# mini-MIDI-hub.net
KiCad netlist of a schematic drawn in EAGLE
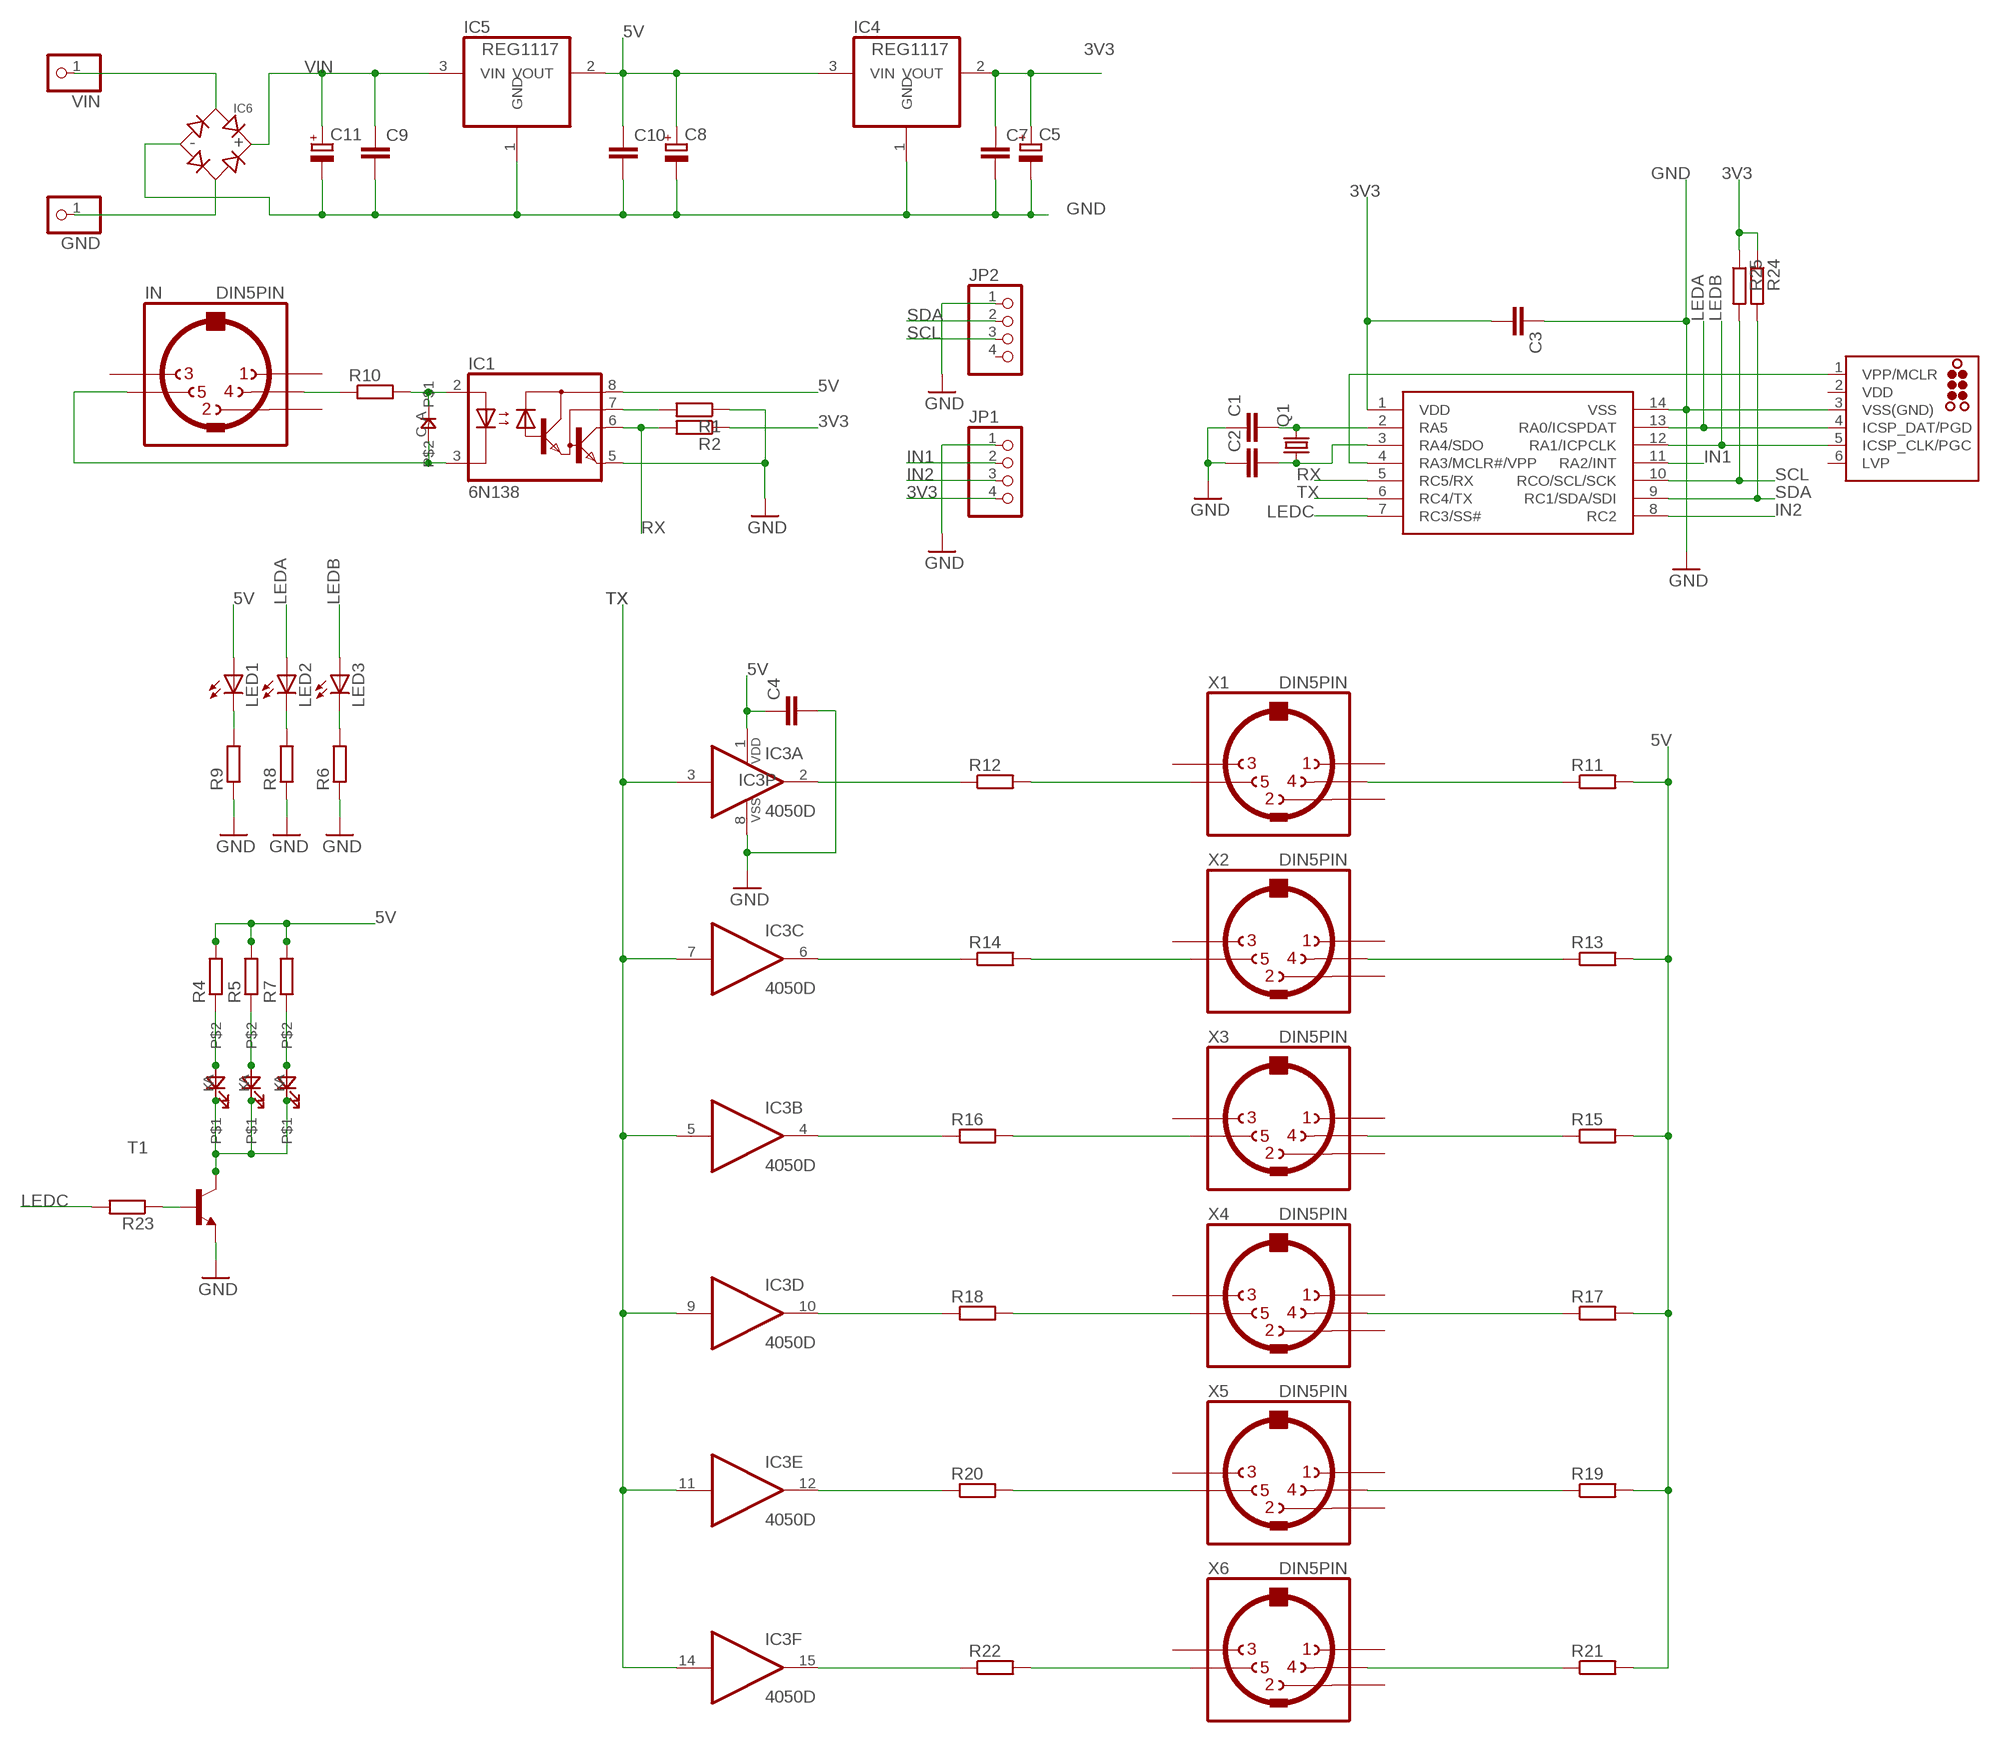
[diagram p0: schematic, sheet 1]

(export (version "E")
  (design (tool "Eeschema 10.0.6"))
  (components
    (comp (ref "C1")
      (value "C-EUC0805")
      (footprint "eagle-import:C0805")
      (libsource (lib "eagle-import") (part "C-EUC0805"))
    )
    (comp (ref "C2")
      (value "C-EUC0805")
      (footprint "eagle-import:C0805")
      (libsource (lib "eagle-import") (part "C-EUC0805"))
    )
    (comp (ref "C3")
      (value "C-EUC0805")
      (footprint "eagle-import:C0805")
      (libsource (lib "eagle-import") (part "C-EUC0805"))
    )
    (comp (ref "C4")
      (value "C-EUC0805")
      (footprint "eagle-import:C0805")
      (libsource (lib "eagle-import") (part "C-EUC0805"))
    )
    (comp (ref "C5")
      (value "CPOL-EUE2-4")
      (footprint "eagle-import:E2-4")
      (libsource (lib "eagle-import") (part "CPOL-EUE2-4"))
    )
    (comp (ref "C7")
      (value "C-EUC0805")
      (footprint "eagle-import:C0805")
      (libsource (lib "eagle-import") (part "C-EUC0805"))
    )
    (comp (ref "C8")
      (value "CPOL-EUE2-4")
      (footprint "eagle-import:E2-4")
      (libsource (lib "eagle-import") (part "CPOL-EUE2-4"))
    )
    (comp (ref "C9")
      (value "C-EUC0805")
      (footprint "eagle-import:C0805")
      (libsource (lib "eagle-import") (part "C-EUC0805"))
    )
    (comp (ref "C10")
      (value "C-EUC0805")
      (footprint "eagle-import:C0805")
      (libsource (lib "eagle-import") (part "C-EUC0805"))
    )
    (comp (ref "C11")
      (value "CPOL-EUE2-4")
      (footprint "eagle-import:E2-4")
      (libsource (lib "eagle-import") (part "CPOL-EUE2-4"))
    )
    (comp (ref "D1")
      (value "0805DIODE")
      (footprint "eagle-import:0805DIODE")
      (libsource (lib "eagle-import") (part "0805DIODE"))
    )
    (comp (ref "GND")
      (value "PINHD-1X1")
      (footprint "eagle-import:1X01")
      (libsource (lib "eagle-import") (part "PINHD-1X1"))
    )
    (comp (ref "IC1")
      (value "6N138")
      (footprint "eagle-import:DIL08")
      (fields (field (name "MF") "VISHAY/TELEFUNKEN"))
      (libsource (lib "eagle-import") (part "6N138"))
    )
    (comp (ref "IC2")
      (value "PIC16F1825SO14")
      (footprint "eagle-import:SO14")
      (libsource (lib "eagle-import") (part "PIC16F1825SO14"))
    )
    (comp (ref "IC3")
      (value "4050D")
      (footprint "eagle-import:SO16")
      (libsource (lib "eagle-import") (part "4050D"))
    )
    (comp (ref "IC4")
      (value "REG1117")
      (footprint "eagle-import:SOT223")
      (libsource (lib "eagle-import") (part "REG1117"))
    )
    (comp (ref "IC5")
      (value "REG1117")
      (footprint "eagle-import:SOT223")
      (libsource (lib "eagle-import") (part "REG1117"))
    )
    (comp (ref "IC6")
      (value "BRIDGERECTIFIER")
      (footprint "eagle-import:SOIC-4")
      (libsource (lib "eagle-import") (part "BRIDGERECTIFIER"))
    )
    (comp (ref "ICSP")
      (value "TC2030-MCP-NL")
      (footprint "eagle-import:TC2030-MCP-NL")
      (libsource (lib "eagle-import") (part "TC2030-MCP-NL"))
    )
    (comp (ref "IN")
      (value "DIN5PIN")
      (footprint "eagle-import:EDGEDIN")
      (libsource (lib "eagle-import") (part "DIN5PIN"))
    )
    (comp (ref "JP1")
      (value "PINHD-1X4")
      (footprint "eagle-import:1X04")
      (libsource (lib "eagle-import") (part "PINHD-1X4"))
    )
    (comp (ref "JP2")
      (value "PINHD-1X4")
      (footprint "eagle-import:1X04")
      (libsource (lib "eagle-import") (part "PINHD-1X4"))
    )
    (comp (ref "LED1")
      (value "LED3MM")
      (footprint "eagle-import:LED3MM")
      (libsource (lib "eagle-import") (part "LED3MM"))
    )
    (comp (ref "LED2")
      (value "LED3MM")
      (footprint "eagle-import:LED3MM")
      (libsource (lib "eagle-import") (part "LED3MM"))
    )
    (comp (ref "LED3")
      (value "LED3MM")
      (footprint "eagle-import:LED3MM")
      (libsource (lib "eagle-import") (part "LED3MM"))
    )
    (comp (ref "Q1")
      (value "CRYSTALHC49S")
      (footprint "eagle-import:HC49_S")
      (libsource (lib "eagle-import") (part "CRYSTALHC49S"))
    )
    (comp (ref "R1")
      (value "R-EU_R0805")
      (footprint "eagle-import:R0805")
      (libsource (lib "eagle-import") (part "R-EU_R0805"))
    )
    (comp (ref "R2")
      (value "R-EU_R0805")
      (footprint "eagle-import:R0805")
      (libsource (lib "eagle-import") (part "R-EU_R0805"))
    )
    (comp (ref "R4")
      (value "R-EU_R0805")
      (footprint "eagle-import:R0805")
      (libsource (lib "eagle-import") (part "R-EU_R0805"))
    )
    (comp (ref "R5")
      (value "R-EU_R0805")
      (footprint "eagle-import:R0805")
      (libsource (lib "eagle-import") (part "R-EU_R0805"))
    )
    (comp (ref "R6")
      (value "R-EU_R0805")
      (footprint "eagle-import:R0805")
      (libsource (lib "eagle-import") (part "R-EU_R0805"))
    )
    (comp (ref "R7")
      (value "R-EU_R0805")
      (footprint "eagle-import:R0805")
      (libsource (lib "eagle-import") (part "R-EU_R0805"))
    )
    (comp (ref "R8")
      (value "R-EU_R0805")
      (footprint "eagle-import:R0805")
      (libsource (lib "eagle-import") (part "R-EU_R0805"))
    )
    (comp (ref "R9")
      (value "R-EU_R0805")
      (footprint "eagle-import:R0805")
      (libsource (lib "eagle-import") (part "R-EU_R0805"))
    )
    (comp (ref "R10")
      (value "R-EU_R0805")
      (footprint "eagle-import:R0805")
      (libsource (lib "eagle-import") (part "R-EU_R0805"))
    )
    (comp (ref "R11")
      (value "R-EU_R0805")
      (footprint "eagle-import:R0805")
      (libsource (lib "eagle-import") (part "R-EU_R0805"))
    )
    (comp (ref "R12")
      (value "R-EU_R0805")
      (footprint "eagle-import:R0805")
      (libsource (lib "eagle-import") (part "R-EU_R0805"))
    )
    (comp (ref "R13")
      (value "R-EU_R0805")
      (footprint "eagle-import:R0805")
      (libsource (lib "eagle-import") (part "R-EU_R0805"))
    )
    (comp (ref "R14")
      (value "R-EU_R0805")
      (footprint "eagle-import:R0805")
      (libsource (lib "eagle-import") (part "R-EU_R0805"))
    )
    (comp (ref "R15")
      (value "R-EU_R0805")
      (footprint "eagle-import:R0805")
      (libsource (lib "eagle-import") (part "R-EU_R0805"))
    )
    (comp (ref "R16")
      (value "R-EU_R0805")
      (footprint "eagle-import:R0805")
      (libsource (lib "eagle-import") (part "R-EU_R0805"))
    )
    (comp (ref "R17")
      (value "R-EU_R0805")
      (footprint "eagle-import:R0805")
      (libsource (lib "eagle-import") (part "R-EU_R0805"))
    )
    (comp (ref "R18")
      (value "R-EU_R0805")
      (footprint "eagle-import:R0805")
      (libsource (lib "eagle-import") (part "R-EU_R0805"))
    )
    (comp (ref "R19")
      (value "R-EU_R0805")
      (footprint "eagle-import:R0805")
      (libsource (lib "eagle-import") (part "R-EU_R0805"))
    )
    (comp (ref "R20")
      (value "R-EU_R0805")
      (footprint "eagle-import:R0805")
      (libsource (lib "eagle-import") (part "R-EU_R0805"))
    )
    (comp (ref "R21")
      (value "R-EU_R0805")
      (footprint "eagle-import:R0805")
      (libsource (lib "eagle-import") (part "R-EU_R0805"))
    )
    (comp (ref "R22")
      (value "R-EU_R0805")
      (footprint "eagle-import:R0805")
      (libsource (lib "eagle-import") (part "R-EU_R0805"))
    )
    (comp (ref "R23")
      (value "R-EU_R0805")
      (footprint "eagle-import:R0805")
      (libsource (lib "eagle-import") (part "R-EU_R0805"))
    )
    (comp (ref "R24")
      (value "R-EU_R0805")
      (footprint "eagle-import:R0805")
      (libsource (lib "eagle-import") (part "R-EU_R0805"))
    )
    (comp (ref "R25")
      (value "R-EU_R0805")
      (footprint "eagle-import:R0805")
      (libsource (lib "eagle-import") (part "R-EU_R0805"))
    )
    (comp (ref "T1")
      (value "MMBT3904LT1-NPN-SOT23-BEC")
      (footprint "eagle-import:SOT23-BEC")
      (libsource (lib "eagle-import") (part "-NPN-SOT23-BECMMBT3904LT1"))
    )
    (comp (ref "U$2")
      (value "LED5MM_EDGE")
      (footprint "eagle-import:LED5MM_EDGE")
      (libsource (lib "eagle-import") (part "LED5MM_EDGE"))
    )
    (comp (ref "U$3")
      (value "LED5MM_EDGE")
      (footprint "eagle-import:LED5MM_EDGE")
      (libsource (lib "eagle-import") (part "LED5MM_EDGE"))
    )
    (comp (ref "U$4")
      (value "LED5MM_EDGE")
      (footprint "eagle-import:LED5MM_EDGE")
      (libsource (lib "eagle-import") (part "LED5MM_EDGE"))
    )
    (comp (ref "VIN")
      (value "PINHD-1X1")
      (footprint "eagle-import:1X01")
      (libsource (lib "eagle-import") (part "PINHD-1X1"))
    )
    (comp (ref "X1")
      (value "DIN5PIN")
      (footprint "eagle-import:EDGEDIN")
      (libsource (lib "eagle-import") (part "DIN5PIN"))
    )
    (comp (ref "X2")
      (value "DIN5PIN")
      (footprint "eagle-import:EDGEDIN")
      (libsource (lib "eagle-import") (part "DIN5PIN"))
    )
    (comp (ref "X3")
      (value "DIN5PIN")
      (footprint "eagle-import:EDGEDIN")
      (libsource (lib "eagle-import") (part "DIN5PIN"))
    )
    (comp (ref "X4")
      (value "DIN5PIN")
      (footprint "eagle-import:EDGEDIN")
      (libsource (lib "eagle-import") (part "DIN5PIN"))
    )
    (comp (ref "X5")
      (value "DIN5PIN")
      (footprint "eagle-import:EDGEDIN")
      (libsource (lib "eagle-import") (part "DIN5PIN"))
    )
    (comp (ref "X6")
      (value "DIN5PIN")
      (footprint "eagle-import:EDGEDIN")
      (libsource (lib "eagle-import") (part "DIN5PIN"))
    )
  )
  (nets
    (net (code "1") (name "/3V3") (class "Default")
      (node (ref "C3") (pin "2") (pinfunction "2_2") (pintype "passive"))
      (node (ref "C5") (pin "+") (pinfunction "+_+") (pintype "passive"))
      (node (ref "C7") (pin "1") (pinfunction "1_1") (pintype "passive"))
      (node (ref "IC2") (pin "1") (pinfunction "VDD_1") (pintype "power_in"))
      (node (ref "IC4") (pin "2") (pinfunction "VOUT_2") (pintype "output"))
      (node (ref "JP1") (pin "4") (pinfunction "4_4") (pintype "passive"))
      (node (ref "R2") (pin "1") (pinfunction "1_1") (pintype "passive"))
      (node (ref "R24") (pin "1") (pinfunction "1_1") (pintype "passive"))
      (node (ref "R25") (pin "1") (pinfunction "1_1") (pintype "passive"))
    )
    (net (code "2") (name "/5V") (class "Default")
      (node (ref "C10") (pin "1") (pinfunction "1_1") (pintype "passive"))
      (node (ref "C4") (pin "1") (pinfunction "1_1") (pintype "passive"))
      (node (ref "C8") (pin "+") (pinfunction "+_+") (pintype "passive"))
      (node (ref "IC1") (pin "8") (pinfunction "VCC_8") (pintype "passive"))
      (node (ref "IC3") (pin "1") (pinfunction "VDD_1") (pintype "power_in"))
      (node (ref "IC4") (pin "3") (pinfunction "VIN_3") (pintype "input"))
      (node (ref "IC5") (pin "2") (pinfunction "VOUT_2") (pintype "output"))
      (node (ref "LED1") (pin "A") (pinfunction "A_A") (pintype "passive"))
      (node (ref "R11") (pin "2") (pinfunction "2_2") (pintype "passive"))
      (node (ref "R13") (pin "2") (pinfunction "2_2") (pintype "passive"))
      (node (ref "R15") (pin "2") (pinfunction "2_2") (pintype "passive"))
      (node (ref "R17") (pin "2") (pinfunction "2_2") (pintype "passive"))
      (node (ref "R19") (pin "2") (pinfunction "2_2") (pintype "passive"))
      (node (ref "R21") (pin "2") (pinfunction "2_2") (pintype "passive"))
      (node (ref "R4") (pin "2") (pinfunction "2_2") (pintype "passive"))
      (node (ref "R5") (pin "2") (pinfunction "2_2") (pintype "passive"))
      (node (ref "R7") (pin "2") (pinfunction "2_2") (pintype "passive"))
    )
    (net (code "3") (name "/IN1") (class "Default")
      (node (ref "IC2") (pin "11") (pinfunction "RA2/INT_11") (pintype "bidirectional"))
      (node (ref "JP1") (pin "2") (pinfunction "2_2") (pintype "passive"))
    )
    (net (code "4") (name "/IN2") (class "Default")
      (node (ref "IC2") (pin "8") (pinfunction "RC2_8") (pintype "bidirectional"))
      (node (ref "JP1") (pin "3") (pinfunction "3_3") (pintype "passive"))
    )
    (net (code "5") (name "/LEDA") (class "Default")
      (node (ref "IC2") (pin "13") (pinfunction "RA0/ICSPDAT_13") (pintype "bidirectional"))
      (node (ref "ICSP") (pin "4") (pinfunction "ICSP_DAT/PGD_4") (pintype "bidirectional"))
      (node (ref "LED2") (pin "A") (pinfunction "A_A") (pintype "passive"))
    )
    (net (code "6") (name "/LEDB") (class "Default")
      (node (ref "IC2") (pin "12") (pinfunction "RA1/ICPCLK_12") (pintype "bidirectional"))
      (node (ref "ICSP") (pin "5") (pinfunction "ICSP_CLK/PGC_5") (pintype "output"))
      (node (ref "LED3") (pin "A") (pinfunction "A_A") (pintype "passive"))
    )
    (net (code "7") (name "/LEDC") (class "Default")
      (node (ref "IC2") (pin "7") (pinfunction "RC3/SS#_7") (pintype "bidirectional"))
      (node (ref "R23") (pin "2") (pinfunction "2_2") (pintype "passive"))
    )
    (net (code "8") (name "/RX") (class "Default")
      (node (ref "IC1") (pin "6") (pinfunction "VO_6") (pintype "passive"))
      (node (ref "IC2") (pin "5") (pinfunction "RC5/RX_5") (pintype "bidirectional"))
      (node (ref "R2") (pin "2") (pinfunction "2_2") (pintype "passive"))
    )
    (net (code "9") (name "/SCL") (class "Default")
      (node (ref "IC2") (pin "10") (pinfunction "RCO/SCL/SCK_10") (pintype "bidirectional"))
      (node (ref "JP2") (pin "3") (pinfunction "3_3") (pintype "passive"))
      (node (ref "R25") (pin "2") (pinfunction "2_2") (pintype "passive"))
    )
    (net (code "10") (name "/SDA") (class "Default")
      (node (ref "IC2") (pin "9") (pinfunction "RC1/SDA/SDI_9") (pintype "bidirectional"))
      (node (ref "JP2") (pin "2") (pinfunction "2_2") (pintype "passive"))
      (node (ref "R24") (pin "2") (pinfunction "2_2") (pintype "passive"))
    )
    (net (code "11") (name "/TX") (class "Default")
      (node (ref "IC2") (pin "6") (pinfunction "RC4/TX_6") (pintype "bidirectional"))
      (node (ref "IC3") (pin "11") (pinfunction "I_11") (pintype "input"))
      (node (ref "IC3") (pin "14") (pinfunction "I_14") (pintype "input"))
      (node (ref "IC3") (pin "3") (pinfunction "I_3") (pintype "input"))
      (node (ref "IC3") (pin "5") (pinfunction "I_5") (pintype "input"))
      (node (ref "IC3") (pin "7") (pinfunction "I_7") (pintype "input"))
      (node (ref "IC3") (pin "9") (pinfunction "I_9") (pintype "input"))
    )
    (net (code "12") (name "/VDD") (class "Default")
      (node (ref "ICSP") (pin "2") (pinfunction "VDD_2") (pintype "power_in"))
    )
    (net (code "13") (name "/VIN") (class "Default")
      (node (ref "C11") (pin "+") (pinfunction "+_+") (pintype "passive"))
      (node (ref "C9") (pin "1") (pinfunction "1_1") (pintype "passive"))
      (node (ref "IC5") (pin "3") (pinfunction "VIN_3") (pintype "input"))
      (node (ref "IC6") (pin "+") (pinfunction "+_+") (pintype "passive"))
    )
    (net (code "14") (name "GND") (class "Default")
      (node (ref "C1") (pin "1") (pinfunction "1_1") (pintype "passive"))
      (node (ref "C10") (pin "2") (pinfunction "2_2") (pintype "passive"))
      (node (ref "C11") (pin "-") (pinfunction "-_-") (pintype "passive"))
      (node (ref "C2") (pin "1") (pinfunction "1_1") (pintype "passive"))
      (node (ref "C3") (pin "1") (pinfunction "1_1") (pintype "passive"))
      (node (ref "C4") (pin "2") (pinfunction "2_2") (pintype "passive"))
      (node (ref "C5") (pin "-") (pinfunction "-_-") (pintype "passive"))
      (node (ref "C7") (pin "2") (pinfunction "2_2") (pintype "passive"))
      (node (ref "C8") (pin "-") (pinfunction "-_-") (pintype "passive"))
      (node (ref "C9") (pin "2") (pinfunction "2_2") (pintype "passive"))
      (node (ref "IC1") (pin "5") (pinfunction "GND_5") (pintype "passive"))
      (node (ref "IC2") (pin "14") (pinfunction "VSS_14") (pintype "power_in"))
      (node (ref "IC3") (pin "8") (pinfunction "VSS_8") (pintype "power_in"))
      (node (ref "IC4") (pin "1") (pinfunction "GND_1") (pintype "power_in"))
      (node (ref "IC5") (pin "1") (pinfunction "GND_1") (pintype "power_in"))
      (node (ref "IC6") (pin "-") (pinfunction "-_-") (pintype "passive"))
      (node (ref "ICSP") (pin "3") (pinfunction "VSS(GND)_3") (pintype "power_in"))
      (node (ref "JP1") (pin "1") (pinfunction "1_1") (pintype "passive"))
      (node (ref "JP2") (pin "1") (pinfunction "1_1") (pintype "passive"))
      (node (ref "R1") (pin "1") (pinfunction "1_1") (pintype "passive"))
      (node (ref "R6") (pin "1") (pinfunction "1_1") (pintype "passive"))
      (node (ref "R8") (pin "1") (pinfunction "1_1") (pintype "passive"))
      (node (ref "R9") (pin "1") (pinfunction "1_1") (pintype "passive"))
      (node (ref "T1") (pin "E") (pinfunction "E_E") (pintype "passive"))
    )
    (net (code "15") (name "Net-(D1-P$1)") (class "Default")
      (node (ref "D1") (pin "C") (pinfunction "P$1_C") (pintype "bidirectional"))
      (node (ref "IC1") (pin "3") (pinfunction "C_3") (pintype "passive"))
      (node (ref "IN") (pin "5") (pinfunction "5_5") (pintype "passive"))
    )
    (net (code "16") (name "Net-(D1-P$2)") (class "Default")
      (node (ref "D1") (pin "A") (pinfunction "P$2_A") (pintype "bidirectional"))
      (node (ref "IC1") (pin "2") (pinfunction "A_2") (pintype "passive"))
      (node (ref "R10") (pin "2") (pinfunction "2_2") (pintype "passive"))
    )
    (net (code "17") (name "Net-(IC1-VB)") (class "Default")
      (node (ref "IC1") (pin "7") (pinfunction "VB_7") (pintype "passive"))
      (node (ref "R1") (pin "2") (pinfunction "2_2") (pintype "passive"))
    )
    (net (code "18") (name "Net-(IC2-RA3{slash}MCLR#{slash}VPP)") (class "Default")
      (node (ref "IC2") (pin "4") (pinfunction "RA3/MCLR#/VPP_4") (pintype "input"))
      (node (ref "ICSP") (pin "1") (pinfunction "VPP/MCLR_1") (pintype "passive"))
    )
    (net (code "19") (name "Net-(IC2-RA4{slash}SDO)") (class "Default")
      (node (ref "C2") (pin "2") (pinfunction "2_2") (pintype "passive"))
      (node (ref "IC2") (pin "3") (pinfunction "RA4/SDO_3") (pintype "bidirectional"))
      (node (ref "Q1") (pin "1") (pinfunction "1_1") (pintype "passive"))
    )
    (net (code "20") (name "Net-(IC2-RA5)") (class "Default")
      (node (ref "C1") (pin "2") (pinfunction "2_2") (pintype "passive"))
      (node (ref "IC2") (pin "2") (pinfunction "RA5_2") (pintype "bidirectional"))
      (node (ref "Q1") (pin "2") (pinfunction "2_2") (pintype "passive"))
    )
    (net (code "21") (name "Net-(IC3A-O)") (class "Default")
      (node (ref "IC3") (pin "2") (pinfunction "O_2") (pintype "output"))
      (node (ref "R12") (pin "1") (pinfunction "1_1") (pintype "passive"))
    )
    (net (code "22") (name "Net-(IC3B-O)") (class "Default")
      (node (ref "IC3") (pin "4") (pinfunction "O_4") (pintype "output"))
      (node (ref "R16") (pin "1") (pinfunction "1_1") (pintype "passive"))
    )
    (net (code "23") (name "Net-(IC3C-O)") (class "Default")
      (node (ref "IC3") (pin "6") (pinfunction "O_6") (pintype "output"))
      (node (ref "R14") (pin "1") (pinfunction "1_1") (pintype "passive"))
    )
    (net (code "24") (name "Net-(IC3D-O)") (class "Default")
      (node (ref "IC3") (pin "10") (pinfunction "O_10") (pintype "output"))
      (node (ref "R18") (pin "1") (pinfunction "1_1") (pintype "passive"))
    )
    (net (code "25") (name "Net-(IC3E-O)") (class "Default")
      (node (ref "IC3") (pin "12") (pinfunction "O_12") (pintype "output"))
      (node (ref "R20") (pin "1") (pinfunction "1_1") (pintype "passive"))
    )
    (net (code "26") (name "Net-(IC3F-O)") (class "Default")
      (node (ref "IC3") (pin "15") (pinfunction "O_15") (pintype "output"))
      (node (ref "R22") (pin "1") (pinfunction "1_1") (pintype "passive"))
    )
    (net (code "27") (name "Net-(IC6-AC1)") (class "Default")
      (node (ref "IC6") (pin "~1") (pinfunction "AC1_~1") (pintype "passive"))
      (node (ref "VIN") (pin "1") (pinfunction "1_1") (pintype "passive"))
    )
    (net (code "28") (name "Net-(IC6-AC2)") (class "Default")
      (node (ref "GND") (pin "1") (pinfunction "1_1") (pintype "passive"))
      (node (ref "IC6") (pin "~2") (pinfunction "AC2_~2") (pintype "passive"))
    )
    (net (code "29") (name "Net-(IN-Pad4)") (class "Default")
      (node (ref "IN") (pin "4") (pinfunction "4_4") (pintype "passive"))
      (node (ref "R10") (pin "1") (pinfunction "1_1") (pintype "passive"))
    )
    (net (code "30") (name "Net-(LED1-C)") (class "Default")
      (node (ref "LED1") (pin "K") (pinfunction "C_K") (pintype "passive"))
      (node (ref "R9") (pin "2") (pinfunction "2_2") (pintype "passive"))
    )
    (net (code "31") (name "Net-(LED2-C)") (class "Default")
      (node (ref "LED2") (pin "K") (pinfunction "C_K") (pintype "passive"))
      (node (ref "R8") (pin "2") (pinfunction "2_2") (pintype "passive"))
    )
    (net (code "32") (name "Net-(LED3-C)") (class "Default")
      (node (ref "LED3") (pin "K") (pinfunction "C_K") (pintype "passive"))
      (node (ref "R6") (pin "2") (pinfunction "2_2") (pintype "passive"))
    )
    (net (code "33") (name "Net-(R11-Pad1)") (class "Default")
      (node (ref "R11") (pin "1") (pinfunction "1_1") (pintype "passive"))
      (node (ref "X1") (pin "4") (pinfunction "4_4") (pintype "passive"))
    )
    (net (code "34") (name "Net-(R12-Pad2)") (class "Default")
      (node (ref "R12") (pin "2") (pinfunction "2_2") (pintype "passive"))
      (node (ref "X1") (pin "5") (pinfunction "5_5") (pintype "passive"))
    )
    (net (code "35") (name "Net-(R13-Pad1)") (class "Default")
      (node (ref "R13") (pin "1") (pinfunction "1_1") (pintype "passive"))
      (node (ref "X2") (pin "4") (pinfunction "4_4") (pintype "passive"))
    )
    (net (code "36") (name "Net-(R14-Pad2)") (class "Default")
      (node (ref "R14") (pin "2") (pinfunction "2_2") (pintype "passive"))
      (node (ref "X2") (pin "5") (pinfunction "5_5") (pintype "passive"))
    )
    (net (code "37") (name "Net-(R15-Pad1)") (class "Default")
      (node (ref "R15") (pin "1") (pinfunction "1_1") (pintype "passive"))
      (node (ref "X3") (pin "4") (pinfunction "4_4") (pintype "passive"))
    )
    (net (code "38") (name "Net-(R16-Pad2)") (class "Default")
      (node (ref "R16") (pin "2") (pinfunction "2_2") (pintype "passive"))
      (node (ref "X3") (pin "5") (pinfunction "5_5") (pintype "passive"))
    )
    (net (code "39") (name "Net-(R17-Pad1)") (class "Default")
      (node (ref "R17") (pin "1") (pinfunction "1_1") (pintype "passive"))
      (node (ref "X4") (pin "4") (pinfunction "4_4") (pintype "passive"))
    )
    (net (code "40") (name "Net-(R18-Pad2)") (class "Default")
      (node (ref "R18") (pin "2") (pinfunction "2_2") (pintype "passive"))
      (node (ref "X4") (pin "5") (pinfunction "5_5") (pintype "passive"))
    )
    (net (code "41") (name "Net-(R19-Pad1)") (class "Default")
      (node (ref "R19") (pin "1") (pinfunction "1_1") (pintype "passive"))
      (node (ref "X5") (pin "4") (pinfunction "4_4") (pintype "passive"))
    )
    (net (code "42") (name "Net-(R20-Pad2)") (class "Default")
      (node (ref "R20") (pin "2") (pinfunction "2_2") (pintype "passive"))
      (node (ref "X5") (pin "5") (pinfunction "5_5") (pintype "passive"))
    )
    (net (code "43") (name "Net-(R21-Pad1)") (class "Default")
      (node (ref "R21") (pin "1") (pinfunction "1_1") (pintype "passive"))
      (node (ref "X6") (pin "4") (pinfunction "4_4") (pintype "passive"))
    )
    (net (code "44") (name "Net-(R22-Pad2)") (class "Default")
      (node (ref "R22") (pin "2") (pinfunction "2_2") (pintype "passive"))
      (node (ref "X6") (pin "5") (pinfunction "5_5") (pintype "passive"))
    )
    (net (code "45") (name "Net-(R23-Pad1)") (class "Default")
      (node (ref "R23") (pin "1") (pinfunction "1_1") (pintype "passive"))
      (node (ref "T1") (pin "B") (pinfunction "B_B") (pintype "passive"))
    )
    (net (code "46") (name "Net-(U$2-P$1)") (class "Default")
      (node (ref "R4") (pin "1") (pinfunction "1_1") (pintype "passive"))
      (node (ref "U$2") (pin "A") (pinfunction "P$1_A") (pintype "bidirectional"))
    )
    (net (code "47") (name "Net-(U$2-P$2)") (class "Default")
      (node (ref "T1") (pin "C") (pinfunction "C_C") (pintype "passive"))
      (node (ref "U$2") (pin "K") (pinfunction "P$2_K") (pintype "bidirectional"))
      (node (ref "U$3") (pin "K") (pinfunction "P$2_K") (pintype "bidirectional"))
      (node (ref "U$4") (pin "K") (pinfunction "P$2_K") (pintype "bidirectional"))
    )
    (net (code "48") (name "Net-(U$3-P$1)") (class "Default")
      (node (ref "R5") (pin "1") (pinfunction "1_1") (pintype "passive"))
      (node (ref "U$3") (pin "A") (pinfunction "P$1_A") (pintype "bidirectional"))
    )
    (net (code "49") (name "Net-(U$4-P$1)") (class "Default")
      (node (ref "R7") (pin "1") (pinfunction "1_1") (pintype "passive"))
      (node (ref "U$4") (pin "A") (pinfunction "P$1_A") (pintype "bidirectional"))
    )
    (net (code "50") (name "unconnected-(ICSP-LVP-Pad6)") (class "Default")
      (node (ref "ICSP") (pin "6") (pinfunction "LVP_6") (pintype "bidirectional"))
    )
    (net (code "51") (name "unconnected-(IN-Pad1)") (class "Default")
      (node (ref "IN") (pin "1") (pinfunction "1_1") (pintype "passive"))
    )
    (net (code "52") (name "unconnected-(IN-Pad2)") (class "Default")
      (node (ref "IN") (pin "2") (pinfunction "2_2") (pintype "passive"))
    )
    (net (code "53") (name "unconnected-(IN-Pad3)") (class "Default")
      (node (ref "IN") (pin "3") (pinfunction "3_3") (pintype "passive"))
    )
    (net (code "54") (name "unconnected-(JP2-Pad4)") (class "Default")
      (node (ref "JP2") (pin "4") (pinfunction "4_4") (pintype "passive"))
    )
    (net (code "55") (name "unconnected-(X1-Pad1)") (class "Default")
      (node (ref "X1") (pin "1") (pinfunction "1_1") (pintype "passive"))
    )
    (net (code "56") (name "unconnected-(X1-Pad2)") (class "Default")
      (node (ref "X1") (pin "2") (pinfunction "2_2") (pintype "passive"))
    )
    (net (code "57") (name "unconnected-(X1-Pad3)") (class "Default")
      (node (ref "X1") (pin "3") (pinfunction "3_3") (pintype "passive"))
    )
    (net (code "58") (name "unconnected-(X2-Pad1)") (class "Default")
      (node (ref "X2") (pin "1") (pinfunction "1_1") (pintype "passive"))
    )
    (net (code "59") (name "unconnected-(X2-Pad2)") (class "Default")
      (node (ref "X2") (pin "2") (pinfunction "2_2") (pintype "passive"))
    )
    (net (code "60") (name "unconnected-(X2-Pad3)") (class "Default")
      (node (ref "X2") (pin "3") (pinfunction "3_3") (pintype "passive"))
    )
    (net (code "61") (name "unconnected-(X3-Pad1)") (class "Default")
      (node (ref "X3") (pin "1") (pinfunction "1_1") (pintype "passive"))
    )
    (net (code "62") (name "unconnected-(X3-Pad2)") (class "Default")
      (node (ref "X3") (pin "2") (pinfunction "2_2") (pintype "passive"))
    )
    (net (code "63") (name "unconnected-(X3-Pad3)") (class "Default")
      (node (ref "X3") (pin "3") (pinfunction "3_3") (pintype "passive"))
    )
    (net (code "64") (name "unconnected-(X4-Pad1)") (class "Default")
      (node (ref "X4") (pin "1") (pinfunction "1_1") (pintype "passive"))
    )
    (net (code "65") (name "unconnected-(X4-Pad2)") (class "Default")
      (node (ref "X4") (pin "2") (pinfunction "2_2") (pintype "passive"))
    )
    (net (code "66") (name "unconnected-(X4-Pad3)") (class "Default")
      (node (ref "X4") (pin "3") (pinfunction "3_3") (pintype "passive"))
    )
    (net (code "67") (name "unconnected-(X5-Pad1)") (class "Default")
      (node (ref "X5") (pin "1") (pinfunction "1_1") (pintype "passive"))
    )
    (net (code "68") (name "unconnected-(X5-Pad2)") (class "Default")
      (node (ref "X5") (pin "2") (pinfunction "2_2") (pintype "passive"))
    )
    (net (code "69") (name "unconnected-(X5-Pad3)") (class "Default")
      (node (ref "X5") (pin "3") (pinfunction "3_3") (pintype "passive"))
    )
    (net (code "70") (name "unconnected-(X6-Pad1)") (class "Default")
      (node (ref "X6") (pin "1") (pinfunction "1_1") (pintype "passive"))
    )
    (net (code "71") (name "unconnected-(X6-Pad2)") (class "Default")
      (node (ref "X6") (pin "2") (pinfunction "2_2") (pintype "passive"))
    )
    (net (code "72") (name "unconnected-(X6-Pad3)") (class "Default")
      (node (ref "X6") (pin "3") (pinfunction "3_3") (pintype "passive"))
    )
  )
)
